# schematic.net
KiCad netlist of a schematic drawn in EAGLE
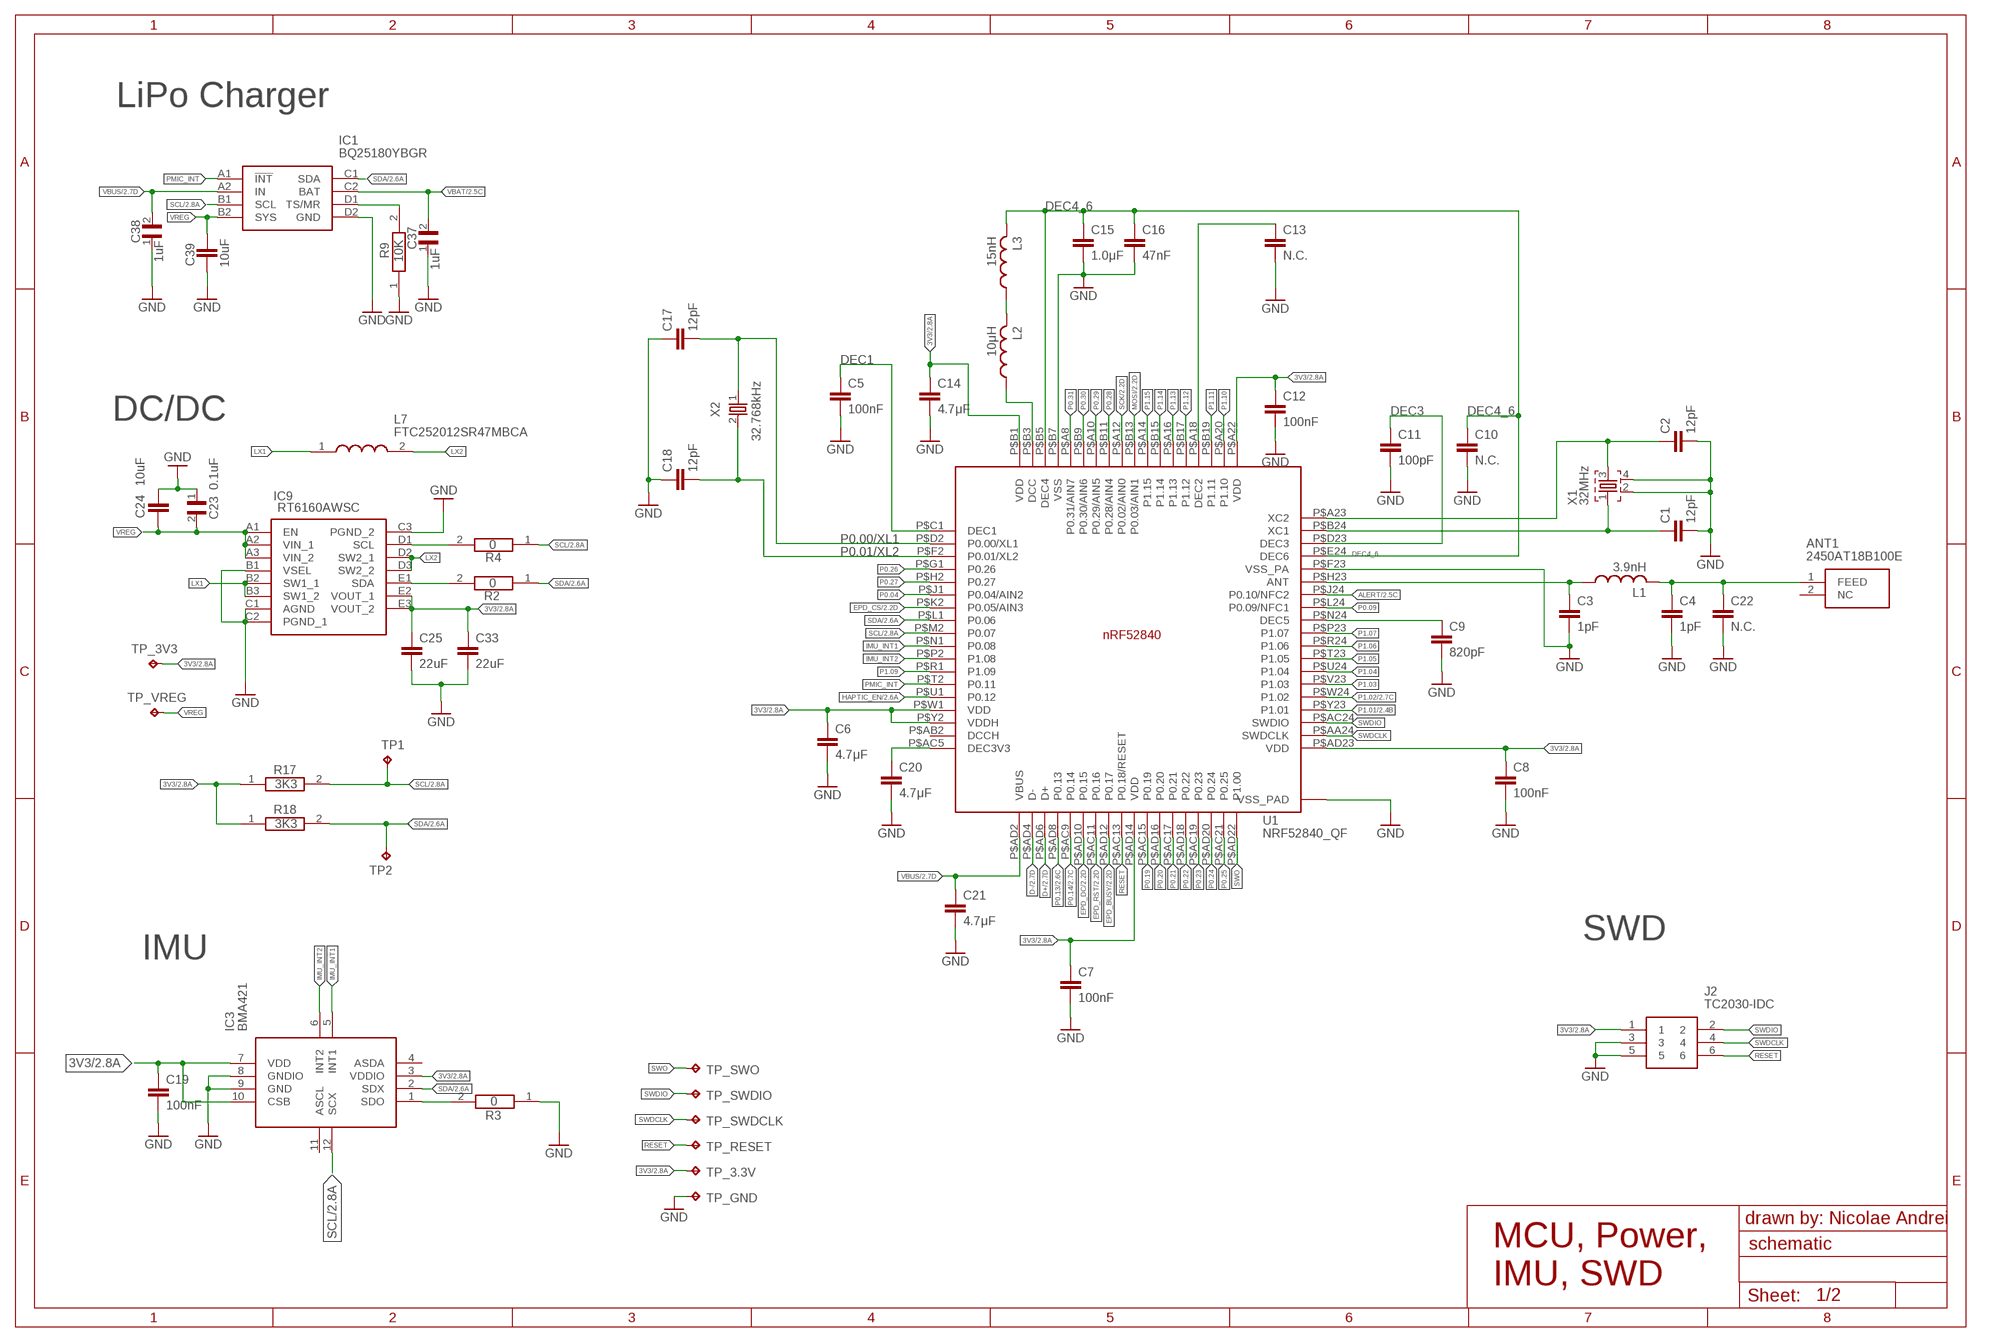
[diagram p0: schematic, sheet 1]
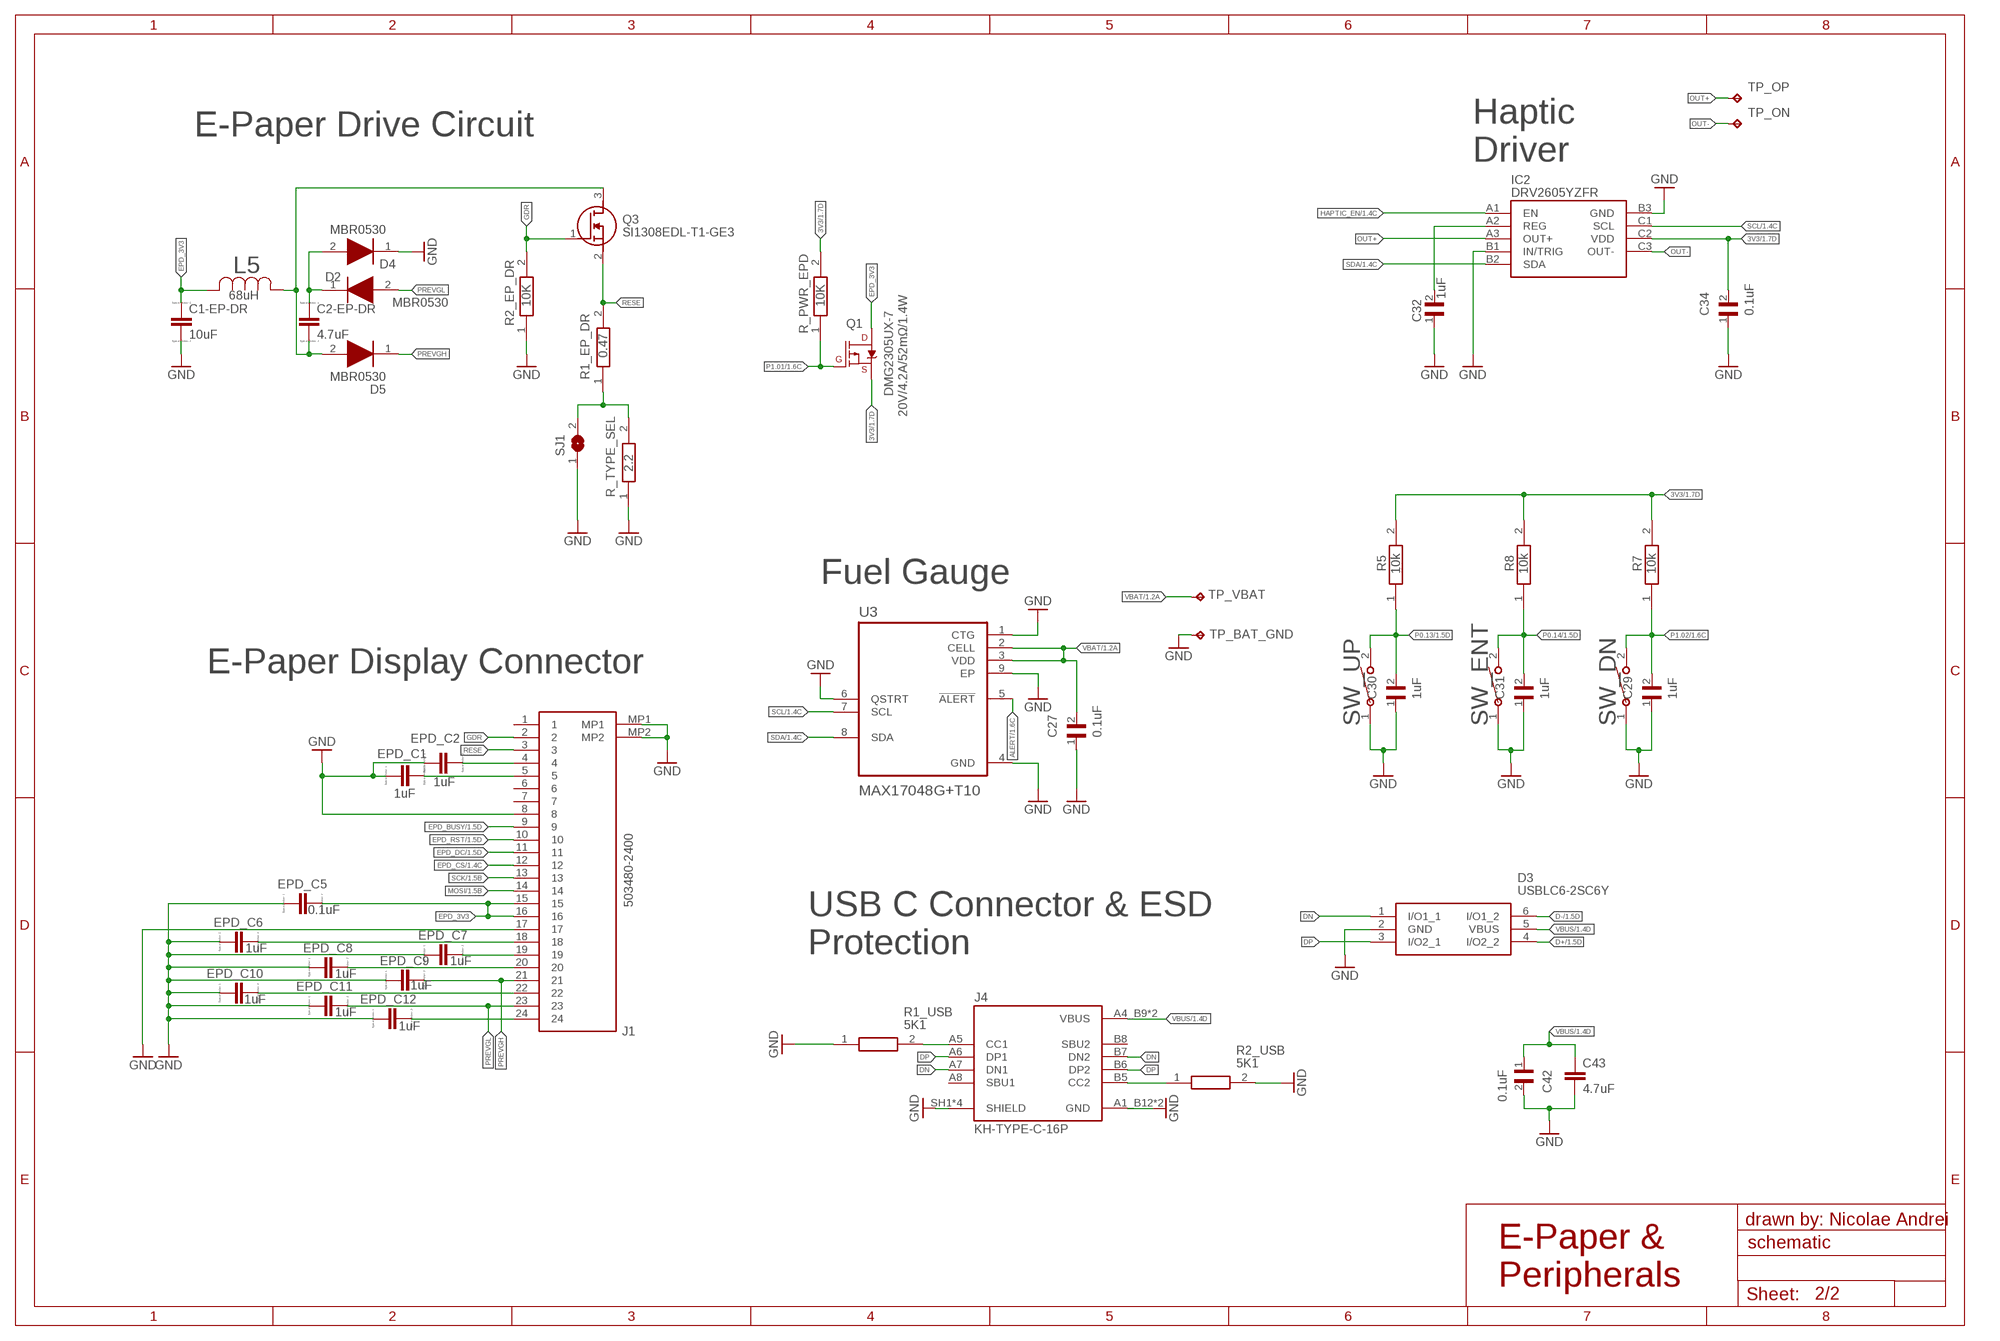
[diagram p1: schematic, sheet 2]

(export (version "E")
  (design (tool "Eeschema 10.0.6"))
  (components
    (comp (ref "C1-EP-DR")
      (value "10uF")
      (footprint "eagle-import:ESP32_C6_LIBRARY_1_ESP32_WROVER_EAGLE-LTSPICE_C0402")
      (libsource (lib "eagle-import") (part "ESP32_C6_LIBRARY_1_ESP32_WROVER_EAGLE-LTSPICE_CC0402"))
    )
    (comp (ref "C2-EP-DR")
      (value "4.7uF")
      (footprint "eagle-import:ESP32_C6_LIBRARY_1_ESP32_WROVER_EAGLE-LTSPICE_C0402")
      (libsource (lib "eagle-import") (part "ESP32_C6_LIBRARY_1_ESP32_WROVER_EAGLE-LTSPICE_CC0402"))
    )
    (comp (ref "C27")
      (value "0.1uF")
      (footprint "eagle-import:GRM011R60J152KE01L_2_CAPC0201X13N")
      (fields (field (name "MF") "Murata") (field (name "MP") "GRM011R60J152KE01L"))
      (libsource (lib "eagle-import") (part "GRM011R60J152KE01L_2_GRM011R60J152KE01L"))
    )
    (comp (ref "C29")
      (value "1uF")
      (footprint "eagle-import:GRM011R60J152KE01L_2_CAPC0201X13N")
      (fields (field (name "MF") "Murata") (field (name "MP") "GRM011R60J152KE01L"))
      (libsource (lib "eagle-import") (part "GRM011R60J152KE01L_2_GRM011R60J152KE01L"))
    )
    (comp (ref "C30")
      (value "1uF")
      (footprint "eagle-import:GRM011R60J152KE01L_2_CAPC0201X13N")
      (fields (field (name "MF") "Murata") (field (name "MP") "GRM011R60J152KE01L"))
      (libsource (lib "eagle-import") (part "GRM011R60J152KE01L_2_GRM011R60J152KE01L"))
    )
    (comp (ref "C31")
      (value "1uF")
      (footprint "eagle-import:GRM011R60J152KE01L_2_CAPC0201X13N")
      (fields (field (name "MF") "Murata") (field (name "MP") "GRM011R60J152KE01L"))
      (libsource (lib "eagle-import") (part "GRM011R60J152KE01L_2_GRM011R60J152KE01L"))
    )
    (comp (ref "C32")
      (value "1uF")
      (footprint "eagle-import:GRM011R60J152KE01L_2_CAPC0201X13N")
      (fields (field (name "MF") "Murata") (field (name "MP") "GRM011R60J152KE01L"))
      (libsource (lib "eagle-import") (part "GRM011R60J152KE01L_2_GRM011R60J152KE01L"))
    )
    (comp (ref "C34")
      (value "0.1uF")
      (footprint "eagle-import:GRM011R60J152KE01L_2_CAPC0201X13N")
      (fields (field (name "MF") "Murata") (field (name "MP") "GRM011R60J152KE01L"))
      (libsource (lib "eagle-import") (part "GRM011R60J152KE01L_2_GRM011R60J152KE01L"))
    )
    (comp (ref "C42")
      (value "0.1uF")
      (footprint "eagle-import:GRM011R60J152KE01L_2_CAPC0201X13N")
      (fields (field (name "MF") "Murata") (field (name "MP") "GRM011R60J152KE01L"))
      (libsource (lib "eagle-import") (part "GRM011R60J152KE01L_2_GRM011R60J152KE01L"))
    )
    (comp (ref "C43")
      (value "4.7uF")
      (footprint "eagle-import:NORDIC_NRF_3_RESC0402_L")
      (libsource (lib "eagle-import") (part "NORDIC_NRF_3_CAPACITOR_0402_L"))
    )
    (comp (ref "D2")
      (value "MBR0530")
      (footprint "eagle-import:ESP32_C6_LIBRARY_5_SOD3716X135N")
      (fields (field (name "MF") "ON Semiconductor"))
      (libsource (lib "eagle-import") (part "ESP32_C6_LIBRARY_5_MBR0530"))
    )
    (comp (ref "D3")
      (value "USBLC6-2SC6Y")
      (footprint "eagle-import:ESP32_C6_LIBRARY_3_SOT95P280X145-6N")
      (fields (field (name "MF") "STMicroelectronics"))
      (libsource (lib "eagle-import") (part "ESP32_C6_LIBRARY_3_USBLC6-2SC6Y"))
    )
    (comp (ref "D4")
      (value "MBR0530")
      (footprint "eagle-import:ESP32_C6_LIBRARY_5_SOD3716X135N")
      (fields (field (name "MF") "ON Semiconductor"))
      (libsource (lib "eagle-import") (part "ESP32_C6_LIBRARY_5_MBR0530"))
    )
    (comp (ref "D5")
      (value "MBR0530")
      (footprint "eagle-import:ESP32_C6_LIBRARY_5_SOD3716X135N")
      (fields (field (name "MF") "ON Semiconductor"))
      (libsource (lib "eagle-import") (part "ESP32_C6_LIBRARY_5_MBR0530"))
    )
    (comp (ref "EPD_C1")
      (value "1uF")
      (footprint "eagle-import:ESP32_C6_LIBRARY_1_ESP32_WROVER_EAGLE-LTSPICE_C0402")
      (libsource (lib "eagle-import") (part "ESP32_C6_LIBRARY_1_ESP32_WROVER_EAGLE-LTSPICE_CC0402"))
    )
    (comp (ref "EPD_C2")
      (value "1uF")
      (footprint "eagle-import:ESP32_C6_LIBRARY_1_ESP32_WROVER_EAGLE-LTSPICE_C0402")
      (libsource (lib "eagle-import") (part "ESP32_C6_LIBRARY_1_ESP32_WROVER_EAGLE-LTSPICE_CC0402"))
    )
    (comp (ref "EPD_C5")
      (value "0.1uF")
      (footprint "eagle-import:ESP32_C6_LIBRARY_1_ESP32_WROVER_EAGLE-LTSPICE_C0402")
      (libsource (lib "eagle-import") (part "ESP32_C6_LIBRARY_1_ESP32_WROVER_EAGLE-LTSPICE_CC0402"))
    )
    (comp (ref "EPD_C6")
      (value "1uF")
      (footprint "eagle-import:ESP32_C6_LIBRARY_1_ESP32_WROVER_EAGLE-LTSPICE_C0402")
      (libsource (lib "eagle-import") (part "ESP32_C6_LIBRARY_1_ESP32_WROVER_EAGLE-LTSPICE_CC0402"))
    )
    (comp (ref "EPD_C7")
      (value "1uF")
      (footprint "eagle-import:ESP32_C6_LIBRARY_1_ESP32_WROVER_EAGLE-LTSPICE_C0402")
      (libsource (lib "eagle-import") (part "ESP32_C6_LIBRARY_1_ESP32_WROVER_EAGLE-LTSPICE_CC0402"))
    )
    (comp (ref "EPD_C8")
      (value "1uF")
      (footprint "eagle-import:ESP32_C6_LIBRARY_1_ESP32_WROVER_EAGLE-LTSPICE_C0402")
      (libsource (lib "eagle-import") (part "ESP32_C6_LIBRARY_1_ESP32_WROVER_EAGLE-LTSPICE_CC0402"))
    )
    (comp (ref "EPD_C9")
      (value "1uF")
      (footprint "eagle-import:ESP32_C6_LIBRARY_1_ESP32_WROVER_EAGLE-LTSPICE_C0402")
      (libsource (lib "eagle-import") (part "ESP32_C6_LIBRARY_1_ESP32_WROVER_EAGLE-LTSPICE_CC0402"))
    )
    (comp (ref "EPD_C10")
      (value "1uF")
      (footprint "eagle-import:ESP32_C6_LIBRARY_1_ESP32_WROVER_EAGLE-LTSPICE_C0402")
      (libsource (lib "eagle-import") (part "ESP32_C6_LIBRARY_1_ESP32_WROVER_EAGLE-LTSPICE_CC0402"))
    )
    (comp (ref "EPD_C11")
      (value "1uF")
      (footprint "eagle-import:ESP32_C6_LIBRARY_1_ESP32_WROVER_EAGLE-LTSPICE_C0402")
      (libsource (lib "eagle-import") (part "ESP32_C6_LIBRARY_1_ESP32_WROVER_EAGLE-LTSPICE_CC0402"))
    )
    (comp (ref "EPD_C12")
      (value "1uF")
      (footprint "eagle-import:ESP32_C6_LIBRARY_1_ESP32_WROVER_EAGLE-LTSPICE_C0402")
      (libsource (lib "eagle-import") (part "ESP32_C6_LIBRARY_1_ESP32_WROVER_EAGLE-LTSPICE_CC0402"))
    )
    (comp (ref "IC2")
      (value "DRV2605YZFR")
      (footprint "eagle-import:DRV2605YZFR_BGA9C50P3X3_144X144X62")
      (libsource (lib "eagle-import") (part "DRV2605YZFR_DRV2605YZFR"))
    )
    (comp (ref "J1")
      (value "503480-2400")
      (footprint "eagle-import:503480-2400_5034802400")
      (fields (field (name "MOUSER_PART_NUMBER") "538-503480-2400"))
      (libsource (lib "eagle-import") (part "503480-2400_503480-2400"))
    )
    (comp (ref "J4")
      (value "KH-TYPE-C-16P")
      (footprint "eagle-import:KH-TYPE-C-16P_KINGHELM_KH-TYPE-C-16P")
      (fields (field (name "MF") "kinghelm"))
      (libsource (lib "eagle-import") (part "KH-TYPE-C-16P_KH-TYPE-C-16P"))
    )
    (comp (ref "L5")
      (value "68uH")
      (footprint "eagle-import:ESP32_C6_LIBRARY_2_IND_4828-WE-TPC_WRE")
      (fields
        (field (name "MANUFACTURER_PART_NUMBER") "744043680")
        (field (name "COPYRIGHT") "Copyright (C) 2024 Ultra Librarian. All rights reserved.")
      )
      (libsource (lib "eagle-import") (part "ESP32_C6_LIBRARY_2_744043680IND_4828-WE-TPC_WRE"))
    )
    (comp (ref "Q1")
      (value "20V/4.2A/52mΩ/1.4W")
      (footprint "eagle-import:ESP32_C6_LIBRARY_4_ESP32_C6_LIBRARY_4_ESP32_C6_LIBRARY_4_ESP32_C6_LIBRARY_4_ESP32_WROVER_SPARKFUN-DISCRETESEMI_SOT23-3")
      (fields (field (name "SPECIFICATII") "DMG2305UX-7"))
      (libsource (lib "eagle-import") (part "ESP32_C6_LIBRARY_4_ESP32_WROVER_SPARKFUN-DISCRETESEMI_MOSFET_PCH-DMG2305UX-7"))
    )
    (comp (ref "Q3")
      (value "SI1308EDL-T1-GE3")
      (footprint "eagle-import:ESP32_C6_LIBRARY_6_SOT65P210X110-3N")
      (fields (field (name "MF") "Vishay Siliconix"))
      (libsource (lib "eagle-import") (part "ESP32_C6_LIBRARY_6_SI1308EDL-T1-GE3"))
    )
    (comp (ref "R1_EP_DR")
      (value "0.47")
      (footprint "eagle-import:CPF0201D7K68C1_0201")
      (libsource (lib "eagle-import") (part "CPF0201D7K68C1_CPF0201D7K68C1"))
    )
    (comp (ref "R1_USB")
      (value "5K1")
      (footprint "eagle-import:CPF0201D7K68C1_0201")
      (libsource (lib "eagle-import") (part "CPF0201D7K68C1_CPF0201D7K68C1"))
    )
    (comp (ref "R2_EP_DR")
      (value "10K")
      (footprint "eagle-import:CPF0201D7K68C1_0201")
      (libsource (lib "eagle-import") (part "CPF0201D7K68C1_CPF0201D7K68C1"))
    )
    (comp (ref "R2_USB")
      (value "5K1")
      (footprint "eagle-import:CPF0201D7K68C1_0201")
      (libsource (lib "eagle-import") (part "CPF0201D7K68C1_CPF0201D7K68C1"))
    )
    (comp (ref "R5")
      (value "10k")
      (footprint "eagle-import:CPF0201D7K68C1_0201")
      (libsource (lib "eagle-import") (part "CPF0201D7K68C1_CPF0201D7K68C1"))
    )
    (comp (ref "R7")
      (value "10k")
      (footprint "eagle-import:CPF0201D7K68C1_0201")
      (libsource (lib "eagle-import") (part "CPF0201D7K68C1_CPF0201D7K68C1"))
    )
    (comp (ref "R8")
      (value "10k")
      (footprint "eagle-import:CPF0201D7K68C1_0201")
      (libsource (lib "eagle-import") (part "CPF0201D7K68C1_CPF0201D7K68C1"))
    )
    (comp (ref "R_PWR_EPD")
      (value "10K")
      (footprint "eagle-import:CPF0201D7K68C1_0201")
      (libsource (lib "eagle-import") (part "CPF0201D7K68C1_CPF0201D7K68C1"))
    )
    (comp (ref "R_TYPE_SEL")
      (value "2.2")
      (footprint "eagle-import:CPF0201D7K68C1_0201")
      (libsource (lib "eagle-import") (part "CPF0201D7K68C1_CPF0201D7K68C1"))
    )
    (comp (ref "SJ1")
      (value "ESP32_C6_LIBRARY_7_JUMPER_SJ")
      (footprint "eagle-import:ESP32_C6_LIBRARY_7_JUMPER_SJ")
      (libsource (lib "eagle-import") (part "ESP32_C6_LIBRARY_7_JUMPER_SJ"))
    )
    (comp (ref "SW_DN")
      (value "2025-10-22_07-23-44_LIBRARY_EVP-AKE31ASW_EVP-AKE31A_PAN")
      (footprint "eagle-import:2025-10-22_07-23-44_LIBRARY_SW_EVP-AKE31A_PAN")
      (fields
        (field (name "MANUFACTURER_PART_NUMBER") "EVP-AKE31A")
        (field (name "COPYRIGHT") "Copyright (C) 2025 Ultra Librarian. All rights reserved.")
      )
      (libsource (lib "eagle-import") (part "2025-10-22_07-23-44_LIBRARY_EVP-AKE31ASW_EVP-AKE31A_PAN"))
    )
    (comp (ref "SW_ENT")
      (value "2025-10-22_07-23-44_LIBRARY_EVP-AKE31ASW_EVP-AKE31A_PAN")
      (footprint "eagle-import:2025-10-22_07-23-44_LIBRARY_SW_EVP-AKE31A_PAN")
      (fields
        (field (name "MANUFACTURER_PART_NUMBER") "EVP-AKE31A")
        (field (name "COPYRIGHT") "Copyright (C) 2025 Ultra Librarian. All rights reserved.")
      )
      (libsource (lib "eagle-import") (part "2025-10-22_07-23-44_LIBRARY_EVP-AKE31ASW_EVP-AKE31A_PAN"))
    )
    (comp (ref "SW_UP")
      (value "2025-10-22_07-23-44_LIBRARY_EVP-AKE31ASW_EVP-AKE31A_PAN")
      (footprint "eagle-import:2025-10-22_07-23-44_LIBRARY_SW_EVP-AKE31A_PAN")
      (fields
        (field (name "MANUFACTURER_PART_NUMBER") "EVP-AKE31A")
        (field (name "COPYRIGHT") "Copyright (C) 2025 Ultra Librarian. All rights reserved.")
      )
      (libsource (lib "eagle-import") (part "2025-10-22_07-23-44_LIBRARY_EVP-AKE31ASW_EVP-AKE31A_PAN"))
    )
    (comp (ref "TP_BAT_GND")
      (value "HECTOR_WATCH_1_TPTP20R")
      (footprint "eagle-import:HECTOR_WATCH_1_TP20R")
      (libsource (lib "eagle-import") (part "HECTOR_WATCH_1_TPTP20R"))
    )
    (comp (ref "TP_ON")
      (value "HECTOR_WATCH_1_TPTP20R")
      (footprint "eagle-import:HECTOR_WATCH_1_TP20R")
      (libsource (lib "eagle-import") (part "HECTOR_WATCH_1_TPTP20R"))
    )
    (comp (ref "TP_OP")
      (value "HECTOR_WATCH_1_TPTP20R")
      (footprint "eagle-import:HECTOR_WATCH_1_TP20R")
      (libsource (lib "eagle-import") (part "HECTOR_WATCH_1_TPTP20R"))
    )
    (comp (ref "TP_VBAT")
      (value "HECTOR_WATCH_1_TPTP20R")
      (footprint "eagle-import:HECTOR_WATCH_1_TP20R")
      (libsource (lib "eagle-import") (part "HECTOR_WATCH_1_TPTP20R"))
    )
    (comp (ref "U3")
      (value "MAX17048G+T10")
      (footprint "eagle-import:ESP32_C6_LIBRARY_SON50P200X200X80-9N")
      (fields (field (name "MF") "Analog Devices"))
      (libsource (lib "eagle-import") (part "ESP32_C6_LIBRARY_MAX17048G+T10"))
    )
    (comp (ref "ANT1")
      (value "2450AT18B100E")
      (footprint "eagle-import:2450AT18B100E_ANTC3216X140N")
      (fields (field (name "MOUSER_PART_NUMBER") "609-2450AT18B100E"))
      (libsource (lib "eagle-import") (part "2450AT18B100E_2450AT18B100E"))
    )
    (comp (ref "C1")
      (value "12pF")
      (footprint "eagle-import:NORDIC_NRF_3_RESC0201_L")
      (libsource (lib "eagle-import") (part "NORDIC_NRF_3_CAPACITOR_0201_L"))
    )
    (comp (ref "C2")
      (value "12pF")
      (footprint "eagle-import:NORDIC_NRF_3_RESC0201_L")
      (libsource (lib "eagle-import") (part "NORDIC_NRF_3_CAPACITOR_0201_L"))
    )
    (comp (ref "C3")
      (value "1pF")
      (footprint "eagle-import:NORDIC_NRF_3_RESC0201_L")
      (libsource (lib "eagle-import") (part "NORDIC_NRF_3_CAPACITOR_0201_L"))
    )
    (comp (ref "C4")
      (value "1pF")
      (footprint "eagle-import:NORDIC_NRF_3_RESC0201_L")
      (libsource (lib "eagle-import") (part "NORDIC_NRF_3_CAPACITOR_0201_L"))
    )
    (comp (ref "C5")
      (value "100nF")
      (footprint "eagle-import:NORDIC_NRF_3_RESC0201_L")
      (libsource (lib "eagle-import") (part "NORDIC_NRF_3_CAPACITOR_0201_L"))
    )
    (comp (ref "C6")
      (value "4.7μF")
      (footprint "eagle-import:NORDIC_NRF_3_RESC0402_L")
      (libsource (lib "eagle-import") (part "NORDIC_NRF_3_CAPACITOR_0402_L"))
    )
    (comp (ref "C7")
      (value "100nF")
      (footprint "eagle-import:NORDIC_NRF_3_RESC0201_L")
      (libsource (lib "eagle-import") (part "NORDIC_NRF_3_CAPACITOR_0201_L"))
    )
    (comp (ref "C8")
      (value "100nF")
      (footprint "eagle-import:NORDIC_NRF_3_RESC0201_L")
      (libsource (lib "eagle-import") (part "NORDIC_NRF_3_CAPACITOR_0201_L"))
    )
    (comp (ref "C9")
      (value "820pF")
      (footprint "eagle-import:NORDIC_NRF_3_RESC0201_L")
      (libsource (lib "eagle-import") (part "NORDIC_NRF_3_CAPACITOR_0201_L"))
    )
    (comp (ref "C10")
      (value "N.C.")
      (footprint "eagle-import:NORDIC_NRF_3_RESC0201_L")
      (libsource (lib "eagle-import") (part "NORDIC_NRF_3_CAPACITOR_0201_L"))
    )
    (comp (ref "C11")
      (value "100pF")
      (footprint "eagle-import:NORDIC_NRF_3_RESC0201_L")
      (libsource (lib "eagle-import") (part "NORDIC_NRF_3_CAPACITOR_0201_L"))
    )
    (comp (ref "C12")
      (value "100nF")
      (footprint "eagle-import:NORDIC_NRF_3_RESC0201_L")
      (libsource (lib "eagle-import") (part "NORDIC_NRF_3_CAPACITOR_0201_L"))
    )
    (comp (ref "C13")
      (value "N.C.")
      (footprint "eagle-import:NORDIC_NRF_3_RESC0201_L")
      (libsource (lib "eagle-import") (part "NORDIC_NRF_3_CAPACITOR_0201_L"))
    )
    (comp (ref "C14")
      (value "4.7μF")
      (footprint "eagle-import:NORDIC_NRF_3_RESC0402_L")
      (libsource (lib "eagle-import") (part "NORDIC_NRF_3_CAPACITOR_0402_L"))
    )
    (comp (ref "C15")
      (value "1.0μF")
      (footprint "eagle-import:NORDIC_NRF_3_RESC0402_L")
      (libsource (lib "eagle-import") (part "NORDIC_NRF_3_CAPACITOR_0402_L"))
    )
    (comp (ref "C16")
      (value "47nF")
      (footprint "eagle-import:NORDIC_NRF_3_RESC0201_L")
      (libsource (lib "eagle-import") (part "NORDIC_NRF_3_CAPACITOR_0201_L"))
    )
    (comp (ref "C17")
      (value "12pF")
      (footprint "eagle-import:NORDIC_NRF_3_RESC0201_L")
      (libsource (lib "eagle-import") (part "NORDIC_NRF_3_CAPACITOR_0201_L"))
    )
    (comp (ref "C18")
      (value "12pF")
      (footprint "eagle-import:NORDIC_NRF_3_RESC0201_L")
      (libsource (lib "eagle-import") (part "NORDIC_NRF_3_CAPACITOR_0201_L"))
    )
    (comp (ref "C19")
      (value "100nF")
      (footprint "eagle-import:NORDIC_NRF_3_RESC0201_L")
      (libsource (lib "eagle-import") (part "NORDIC_NRF_3_CAPACITOR_0201_L"))
    )
    (comp (ref "C20")
      (value "4.7μF")
      (footprint "eagle-import:NORDIC_NRF_3_RESC0402_L")
      (libsource (lib "eagle-import") (part "NORDIC_NRF_3_CAPACITOR_0402_L"))
    )
    (comp (ref "C21")
      (value "4.7μF")
      (footprint "eagle-import:NORDIC_NRF_3_RESC0402_L")
      (libsource (lib "eagle-import") (part "NORDIC_NRF_3_CAPACITOR_0402_L"))
    )
    (comp (ref "C22")
      (value "N.C.")
      (footprint "eagle-import:NORDIC_NRF_3_RESC0201_L")
      (libsource (lib "eagle-import") (part "NORDIC_NRF_3_CAPACITOR_0201_L"))
    )
    (comp (ref "C23")
      (value "0.1uF")
      (footprint "eagle-import:GRM011R60J152KE01L_1_0201")
      (libsource (lib "eagle-import") (part "GRM011R60J152KE01L_1_GRM011R60J152KE01L"))
    )
    (comp (ref "C24")
      (value "10uF")
      (footprint "eagle-import:PERFECT_0402_0402")
      (libsource (lib "eagle-import") (part "PERFECT_0402_CAP_0402"))
    )
    (comp (ref "C25")
      (value "22uF")
      (footprint "eagle-import:PERFECT_0402_0402")
      (libsource (lib "eagle-import") (part "PERFECT_0402_CAP_0402"))
    )
    (comp (ref "C33")
      (value "22uF")
      (footprint "eagle-import:PERFECT_0402_0402")
      (libsource (lib "eagle-import") (part "PERFECT_0402_CAP_0402"))
    )
    (comp (ref "C37")
      (value "1uF")
      (footprint "eagle-import:GRM011R60J152KE01L_1_0201")
      (libsource (lib "eagle-import") (part "GRM011R60J152KE01L_1_GRM011R60J152KE01L"))
    )
    (comp (ref "C38")
      (value "1uF")
      (footprint "eagle-import:GRM011R60J152KE01L_1_0201")
      (libsource (lib "eagle-import") (part "GRM011R60J152KE01L_1_GRM011R60J152KE01L"))
    )
    (comp (ref "C39")
      (value "10uF")
      (footprint "eagle-import:PERFECT_0402_0402")
      (libsource (lib "eagle-import") (part "PERFECT_0402_CAP_0402"))
    )
    (comp (ref "IC1")
      (value "BQ25180YBGR")
      (footprint "eagle-import:BQ25180YBGR_BGA8C40P2X4_100X155X50")
      (fields (field (name "MOUSER_PART_NUMBER") "595-BQ25180YBGR"))
      (libsource (lib "eagle-import") (part "BQ25180YBGR_BQ25180YBGR"))
    )
    (comp (ref "IC3")
      (value "BMA421")
      (footprint "eagle-import:BMA423_BMA423")
      (fields (field (name "ARROW_PART_NUMBER") "BMA423") (field (name "MOUSER_PART_NUMBER") "262-BMA423"))
      (libsource (lib "eagle-import") (part "BMA423_BMA423"))
    )
    (comp (ref "IC9")
      (value "RT6160AWSC")
      (footprint "eagle-import:RT6160AWSC_BGA15C40P3X5_140X230X60")
      (fields (field (name "MOUSER_PART_NUMBER") "835-RT6160AWSC"))
      (libsource (lib "eagle-import") (part "RT6160AWSC_RT6160AWSC"))
    )
    (comp (ref "J2")
      (value "TC2030-IDC")
      (footprint "eagle-import:TC2030-IDC_TC2030IDC")
      (libsource (lib "eagle-import") (part "TC2030-IDC_TC2030-IDC"))
    )
    (comp (ref "L1")
      (value "3.9nH")
      (footprint "eagle-import:NORDIC_NRF_2_RESC0402_L")
      (libsource (lib "eagle-import") (part "NORDIC_NRF_2_INDUCTOR_0402_L"))
    )
    (comp (ref "L2")
      (value "10μH")
      (footprint "eagle-import:NORDIC_NRF_2_RESC0402_L")
      (libsource (lib "eagle-import") (part "NORDIC_NRF_2_INDUCTOR_0402_L"))
    )
    (comp (ref "L3")
      (value "15nH")
      (footprint "eagle-import:NORDIC_NRF_2_RESC0402_L")
      (libsource (lib "eagle-import") (part "NORDIC_NRF_2_INDUCTOR_0402_L"))
    )
    (comp (ref "L7")
      (value "FTC252012SR47MBCA")
      (footprint "eagle-import:MLP2016SR47MT0S1_INDC2016X100N")
      (libsource (lib "eagle-import") (part "MLP2016SR47MT0S1_FTC252012SR47MBCA"))
    )
    (comp (ref "R2")
      (value "0")
      (footprint "eagle-import:CPF0201D7K68C1_0201")
      (libsource (lib "eagle-import") (part "CPF0201D7K68C1_CPF0201D7K68C1"))
    )
    (comp (ref "R3")
      (value "0")
      (footprint "eagle-import:CPF0201D7K68C1_0201")
      (libsource (lib "eagle-import") (part "CPF0201D7K68C1_CPF0201D7K68C1"))
    )
    (comp (ref "R4")
      (value "0")
      (footprint "eagle-import:CPF0201D7K68C1_0201")
      (libsource (lib "eagle-import") (part "CPF0201D7K68C1_CPF0201D7K68C1"))
    )
    (comp (ref "R9")
      (value "10K")
      (footprint "eagle-import:CPF0201D7K68C1_0201")
      (libsource (lib "eagle-import") (part "CPF0201D7K68C1_CPF0201D7K68C1"))
    )
    (comp (ref "R17")
      (value "3K3")
      (footprint "eagle-import:CPF0201D7K68C1_0201")
      (libsource (lib "eagle-import") (part "CPF0201D7K68C1_CPF0201D7K68C1"))
    )
    (comp (ref "R18")
      (value "3K3")
      (footprint "eagle-import:CPF0201D7K68C1_0201")
      (libsource (lib "eagle-import") (part "CPF0201D7K68C1_CPF0201D7K68C1"))
    )
    (comp (ref "TP1")
      (value "HECTOR_WATCH_1_TPTP20R")
      (footprint "eagle-import:HECTOR_WATCH_1_TP20R")
      (libsource (lib "eagle-import") (part "HECTOR_WATCH_1_TPTP20R"))
    )
    (comp (ref "TP2")
      (value "HECTOR_WATCH_1_TPTP20R")
      (footprint "eagle-import:HECTOR_WATCH_1_TP20R")
      (libsource (lib "eagle-import") (part "HECTOR_WATCH_1_TPTP20R"))
    )
    (comp (ref "TP_3.3V")
      (value "HECTOR_WATCH_1_TPTP20R")
      (footprint "eagle-import:HECTOR_WATCH_1_TP20R")
      (libsource (lib "eagle-import") (part "HECTOR_WATCH_1_TPTP20R"))
    )
    (comp (ref "TP_3V3")
      (value "HECTOR_WATCH_1_TPTP20R")
      (footprint "eagle-import:HECTOR_WATCH_1_TP20R")
      (libsource (lib "eagle-import") (part "HECTOR_WATCH_1_TPTP20R"))
    )
    (comp (ref "TP_GND")
      (value "HECTOR_WATCH_1_TPTP20R")
      (footprint "eagle-import:HECTOR_WATCH_1_TP20R")
      (libsource (lib "eagle-import") (part "HECTOR_WATCH_1_TPTP20R"))
    )
    (comp (ref "TP_RESET")
      (value "HECTOR_WATCH_1_TPTP20R")
      (footprint "eagle-import:HECTOR_WATCH_1_TP20R")
      (libsource (lib "eagle-import") (part "HECTOR_WATCH_1_TPTP20R"))
    )
    (comp (ref "TP_SWDCLK")
      (value "HECTOR_WATCH_1_TPTP20R")
      (footprint "eagle-import:HECTOR_WATCH_1_TP20R")
      (libsource (lib "eagle-import") (part "HECTOR_WATCH_1_TPTP20R"))
    )
    (comp (ref "TP_SWDIO")
      (value "HECTOR_WATCH_1_TPTP20R")
      (footprint "eagle-import:HECTOR_WATCH_1_TP20R")
      (libsource (lib "eagle-import") (part "HECTOR_WATCH_1_TPTP20R"))
    )
    (comp (ref "TP_SWO")
      (value "HECTOR_WATCH_1_TPTP20R")
      (footprint "eagle-import:HECTOR_WATCH_1_TP20R")
      (libsource (lib "eagle-import") (part "HECTOR_WATCH_1_TPTP20R"))
    )
    (comp (ref "TP_VREG")
      (value "HECTOR_WATCH_1_TPTP20R")
      (footprint "eagle-import:HECTOR_WATCH_1_TP20R")
      (libsource (lib "eagle-import") (part "HECTOR_WATCH_1_TPTP20R"))
    )
    (comp (ref "U1")
      (value "NRF52840_QF")
      (footprint "eagle-import:NORDIC_NRF_4_AQFN50P700X700X85_HS-74N")
      (libsource (lib "eagle-import") (part "NORDIC_NRF_4_NRF52840_QF"))
    )
    (comp (ref "X1")
      (value "32MHz")
      (footprint "eagle-import:NORDIC_NRF_BT-XTAL_2016_N")
      (libsource (lib "eagle-import") (part "NORDIC_NRF_XTAL_32MHZ"))
    )
    (comp (ref "X2")
      (value "32.768kHz")
      (footprint "eagle-import:NORDIC_NRF_1_XTAL_3215_N")
      (libsource (lib "eagle-import") (part "NORDIC_NRF_1_XTAL_32KHZ"))
    )
  )
  (nets
    (net (code "1") (name "3V3") (class "Default")
      (node (ref "C12") (pin "1") (pinfunction "1_1") (pintype "passive"))
      (node (ref "C14") (pin "1") (pinfunction "1_1") (pintype "passive"))
      (node (ref "C19") (pin "1") (pinfunction "1_1") (pintype "passive"))
      (node (ref "C25") (pin "1") (pinfunction "1_1") (pintype "passive"))
      (node (ref "C33") (pin "1") (pinfunction "1_1") (pintype "passive"))
      (node (ref "C34") (pin "2") (pinfunction "2_2") (pintype "passive"))
      (node (ref "C6") (pin "1") (pinfunction "1_1") (pintype "passive"))
      (node (ref "C7") (pin "1") (pinfunction "1_1") (pintype "passive"))
      (node (ref "C8") (pin "1") (pinfunction "1_1") (pintype "passive"))
      (node (ref "IC2") (pin "C2") (pinfunction "VDD_C2") (pintype "bidirectional"))
      (node (ref "IC3") (pin "10") (pinfunction "CSB_10") (pintype "bidirectional"))
      (node (ref "IC3") (pin "3") (pinfunction "VDDIO_3") (pintype "bidirectional"))
      (node (ref "IC3") (pin "7") (pinfunction "VDD_7") (pintype "bidirectional"))
      (node (ref "IC9") (pin "E2") (pinfunction "VOUT_1_E2") (pintype "bidirectional"))
      (node (ref "IC9") (pin "E3") (pinfunction "VOUT_2_E3") (pintype "bidirectional"))
      (node (ref "J2") (pin "1") (pinfunction "1_1") (pintype "bidirectional"))
      (node (ref "Q1") (pin "2") (pinfunction "S_2") (pintype "bidirectional"))
      (node (ref "R17") (pin "1") (pinfunction "1_1") (pintype "bidirectional"))
      (node (ref "R18") (pin "1") (pinfunction "1_1") (pintype "bidirectional"))
      (node (ref "R5") (pin "2") (pinfunction "2_2") (pintype "bidirectional"))
      (node (ref "R7") (pin "2") (pinfunction "2_2") (pintype "bidirectional"))
      (node (ref "R8") (pin "2") (pinfunction "2_2") (pintype "bidirectional"))
      (node (ref "R_PWR_EPD") (pin "2") (pinfunction "2_2") (pintype "bidirectional"))
      (node (ref "TP_3.3V") (pin "TP") (pinfunction "TP_TP") (pintype "input"))
      (node (ref "TP_3V3") (pin "TP") (pinfunction "TP_TP") (pintype "input"))
      (node (ref "U1") (pin "P$A22") (pinfunction "VDD_P$A22") (pintype "power_in"))
      (node (ref "U1") (pin "P$AD14") (pinfunction "VDD_P$AD14") (pintype "power_in"))
      (node (ref "U1") (pin "P$AD23") (pinfunction "VDD_P$AD23") (pintype "power_in"))
      (node (ref "U1") (pin "P$B1") (pinfunction "VDD_P$B1") (pintype "power_in"))
      (node (ref "U1") (pin "P$W1") (pinfunction "VDD_P$W1") (pintype "power_in"))
      (node (ref "U1") (pin "P$Y2") (pinfunction "VDDH_P$Y2") (pintype "power_in"))
    )
    (net (code "2") (name "ALERT") (class "Default")
      (node (ref "U1") (pin "P$J24") (pinfunction "P0.10/NFC2_P$J24") (pintype "bidirectional"))
      (node (ref "U3") (pin "5") (pinfunction "~{ALERT}_5") (pintype "output"))
    )
    (net (code "3") (name "D+") (class "Default")
      (node (ref "D3") (pin "4") (pinfunction "I/O2_2_4") (pintype "bidirectional"))
      (node (ref "U1") (pin "P$AD6") (pinfunction "D+_P$AD6") (pintype "bidirectional"))
    )
    (net (code "4") (name "D-") (class "Default")
      (node (ref "D3") (pin "6") (pinfunction "I/O1_2_6") (pintype "bidirectional"))
      (node (ref "U1") (pin "P$AD4") (pinfunction "D-_P$AD4") (pintype "bidirectional"))
    )
    (net (code "5") (name "DEC1") (class "Default")
      (node (ref "C5") (pin "1") (pinfunction "1_1") (pintype "passive"))
      (node (ref "U1") (pin "P$C1") (pinfunction "DEC1_P$C1") (pintype "power_in"))
    )
    (net (code "6") (name "DEC3") (class "Default")
      (node (ref "C11") (pin "1") (pinfunction "1_1") (pintype "passive"))
      (node (ref "U1") (pin "P$D23") (pinfunction "DEC3_P$D23") (pintype "bidirectional"))
    )
    (net (code "7") (name "DEC4_6") (class "Default")
      (node (ref "C10") (pin "1") (pinfunction "1_1") (pintype "passive"))
      (node (ref "C15") (pin "1") (pinfunction "1_1") (pintype "passive"))
      (node (ref "C16") (pin "1") (pinfunction "1_1") (pintype "passive"))
      (node (ref "L3") (pin "2") (pinfunction "2_2") (pintype "passive"))
      (node (ref "U1") (pin "P$B5") (pinfunction "DEC4_P$B5") (pintype "power_in"))
      (node (ref "U1") (pin "P$E24") (pinfunction "DEC6_P$E24") (pintype "bidirectional"))
    )
    (net (code "8") (name "DN") (class "Default")
      (node (ref "D3") (pin "1") (pinfunction "I/O1_1_1") (pintype "bidirectional"))
      (node (ref "J4") (pin "A7") (pinfunction "DN1_A7") (pintype "bidirectional"))
      (node (ref "J4") (pin "B7") (pinfunction "DN2_B7") (pintype "bidirectional"))
    )
    (net (code "9") (name "DP") (class "Default")
      (node (ref "D3") (pin "3") (pinfunction "I/O2_1_3") (pintype "bidirectional"))
      (node (ref "J4") (pin "A6") (pinfunction "DP1_A6") (pintype "bidirectional"))
      (node (ref "J4") (pin "B6") (pinfunction "DP2_B6") (pintype "bidirectional"))
    )
    (net (code "10") (name "EPD_3V3") (class "Default")
      (node (ref "C1-EP-DR") (pin "1") (pinfunction "1_1") (pintype "passive"))
      (node (ref "EPD_C5") (pin "2") (pinfunction "2_2") (pintype "passive"))
      (node (ref "J1") (pin "15") (pinfunction "15_15") (pintype "bidirectional"))
      (node (ref "J1") (pin "16") (pinfunction "16_16") (pintype "bidirectional"))
      (node (ref "L5") (pin "2") (pinfunction "2_2") (pintype "passive"))
      (node (ref "Q1") (pin "3") (pinfunction "D_3") (pintype "bidirectional"))
    )
    (net (code "11") (name "EPD_BUSY") (class "Default")
      (node (ref "J1") (pin "9") (pinfunction "9_9") (pintype "bidirectional"))
      (node (ref "U1") (pin "P$AD12") (pinfunction "P0.17_P$AD12") (pintype "bidirectional"))
    )
    (net (code "12") (name "EPD_CS") (class "Default")
      (node (ref "J1") (pin "12") (pinfunction "12_12") (pintype "bidirectional"))
      (node (ref "U1") (pin "P$K2") (pinfunction "P0.05/AIN3_P$K2") (pintype "bidirectional"))
    )
    (net (code "13") (name "EPD_DC") (class "Default")
      (node (ref "J1") (pin "11") (pinfunction "11_11") (pintype "bidirectional"))
      (node (ref "U1") (pin "P$AD10") (pinfunction "P0.15_P$AD10") (pintype "bidirectional"))
    )
    (net (code "14") (name "EPD_RST") (class "Default")
      (node (ref "J1") (pin "10") (pinfunction "10_10") (pintype "bidirectional"))
      (node (ref "U1") (pin "P$AC11") (pinfunction "P0.16_P$AC11") (pintype "bidirectional"))
    )
    (net (code "15") (name "GDR") (class "Default")
      (node (ref "J1") (pin "2") (pinfunction "2_2") (pintype "bidirectional"))
      (node (ref "Q3") (pin "1") (pinfunction "G_1") (pintype "bidirectional"))
      (node (ref "R2_EP_DR") (pin "2") (pinfunction "2_2") (pintype "bidirectional"))
    )
    (net (code "16") (name "GND") (class "Default")
      (node (ref "C1") (pin "2") (pinfunction "2_2") (pintype "passive"))
      (node (ref "C1-EP-DR") (pin "2") (pinfunction "2_2") (pintype "passive"))
      (node (ref "C10") (pin "2") (pinfunction "2_2") (pintype "passive"))
      (node (ref "C11") (pin "2") (pinfunction "2_2") (pintype "passive"))
      (node (ref "C12") (pin "2") (pinfunction "2_2") (pintype "passive"))
      (node (ref "C13") (pin "2") (pinfunction "2_2") (pintype "passive"))
      (node (ref "C14") (pin "2") (pinfunction "2_2") (pintype "passive"))
      (node (ref "C15") (pin "2") (pinfunction "2_2") (pintype "passive"))
      (node (ref "C16") (pin "2") (pinfunction "2_2") (pintype "passive"))
      (node (ref "C17") (pin "1") (pinfunction "1_1") (pintype "passive"))
      (node (ref "C18") (pin "1") (pinfunction "1_1") (pintype "passive"))
      (node (ref "C19") (pin "2") (pinfunction "2_2") (pintype "passive"))
      (node (ref "C2") (pin "2") (pinfunction "2_2") (pintype "passive"))
      (node (ref "C20") (pin "2") (pinfunction "2_2") (pintype "passive"))
      (node (ref "C21") (pin "2") (pinfunction "2_2") (pintype "passive"))
      (node (ref "C22") (pin "2") (pinfunction "2_2") (pintype "passive"))
      (node (ref "C23") (pin "1") (pinfunction "1_1") (pintype "passive"))
      (node (ref "C24") (pin "1") (pinfunction "1_1") (pintype "passive"))
      (node (ref "C25") (pin "2") (pinfunction "2_2") (pintype "passive"))
      (node (ref "C27") (pin "1") (pinfunction "1_1") (pintype "passive"))
      (node (ref "C29") (pin "1") (pinfunction "1_1") (pintype "passive"))
      (node (ref "C3") (pin "2") (pinfunction "2_2") (pintype "passive"))
      (node (ref "C30") (pin "1") (pinfunction "1_1") (pintype "passive"))
      (node (ref "C31") (pin "1") (pinfunction "1_1") (pintype "passive"))
      (node (ref "C32") (pin "1") (pinfunction "1_1") (pintype "passive"))
      (node (ref "C33") (pin "2") (pinfunction "2_2") (pintype "passive"))
      (node (ref "C34") (pin "1") (pinfunction "1_1") (pintype "passive"))
      (node (ref "C37") (pin "1") (pinfunction "1_1") (pintype "passive"))
      (node (ref "C38") (pin "1") (pinfunction "1_1") (pintype "passive"))
      (node (ref "C39") (pin "2") (pinfunction "2_2") (pintype "passive"))
      (node (ref "C4") (pin "2") (pinfunction "2_2") (pintype "passive"))
      (node (ref "C42") (pin "2") (pinfunction "2_2") (pintype "passive"))
      (node (ref "C43") (pin "2") (pinfunction "2_2") (pintype "passive"))
      (node (ref "C5") (pin "2") (pinfunction "2_2") (pintype "passive"))
      (node (ref "C6") (pin "2") (pinfunction "2_2") (pintype "passive"))
      (node (ref "C7") (pin "2") (pinfunction "2_2") (pintype "passive"))
      (node (ref "C8") (pin "2") (pinfunction "2_2") (pintype "passive"))
      (node (ref "C9") (pin "2") (pinfunction "2_2") (pintype "passive"))
      (node (ref "D2") (pin "1") (pinfunction "K_1") (pintype "bidirectional"))
      (node (ref "D3") (pin "2") (pinfunction "GND_2") (pintype "bidirectional"))
      (node (ref "EPD_C1") (pin "1") (pinfunction "1_1") (pintype "passive"))
      (node (ref "EPD_C10") (pin "1") (pinfunction "1_1") (pintype "passive"))
      (node (ref "EPD_C11") (pin "1") (pinfunction "1_1") (pintype "passive"))
      (node (ref "EPD_C12") (pin "1") (pinfunction "1_1") (pintype "passive"))
      (node (ref "EPD_C2") (pin "1") (pinfunction "1_1") (pintype "passive"))
      (node (ref "EPD_C5") (pin "1") (pinfunction "1_1") (pintype "passive"))
      (node (ref "EPD_C6") (pin "1") (pinfunction "1_1") (pintype "passive"))
      (node (ref "EPD_C7") (pin "1") (pinfunction "1_1") (pintype "passive"))
      (node (ref "EPD_C8") (pin "1") (pinfunction "1_1") (pintype "passive"))
      (node (ref "EPD_C9") (pin "1") (pinfunction "1_1") (pintype "passive"))
      (node (ref "IC1") (pin "D2") (pinfunction "GND_D2") (pintype "bidirectional"))
      (node (ref "IC2") (pin "B1") (pinfunction "IN/TRIG_B1") (pintype "bidirectional"))
      (node (ref "IC2") (pin "B3") (pinfunction "GND_B3") (pintype "bidirectional"))
      (node (ref "IC3") (pin "8") (pinfunction "GNDIO_8") (pintype "bidirectional"))
      (node (ref "IC3") (pin "9") (pinfunction "GND_9") (pintype "bidirectional"))
      (node (ref "IC9") (pin "B1") (pinfunction "VSEL_B1") (pintype "bidirectional"))
      (node (ref "IC9") (pin "C1") (pinfunction "AGND_C1") (pintype "bidirectional"))
      (node (ref "IC9") (pin "C2") (pinfunction "PGND_1_C2") (pintype "bidirectional"))
      (node (ref "IC9") (pin "C3") (pinfunction "PGND_2_C3") (pintype "bidirectional"))
      (node (ref "J1") (pin "17") (pinfunction "17_17") (pintype "bidirectional"))
      (node (ref "J1") (pin "8") (pinfunction "8_8") (pintype "bidirectional"))
      (node (ref "J1") (pin "MP1") (pinfunction "MP1_MP1") (pintype "bidirectional"))
      (node (ref "J1") (pin "MP2") (pinfunction "MP2_MP2") (pintype "bidirectional"))
      (node (ref "J2") (pin "3") (pinfunction "3_3") (pintype "bidirectional"))
      (node (ref "J2") (pin "5") (pinfunction "5_5") (pintype "bidirectional"))
      (node (ref "J4") (pin "A12_B1") (pinfunction "GND_A12_B1") (pintype "power_in"))
      (node (ref "J4") (pin "A1_B12") (pinfunction "GND_A1_B12") (pintype "power_in"))
      (node (ref "J4") (pin "SH1") (pinfunction "SHIELD_SH1") (pintype "passive"))
      (node (ref "J4") (pin "SH2") (pinfunction "SHIELD_SH2") (pintype "passive"))
      (node (ref "J4") (pin "SH3") (pinfunction "SHIELD_SH3") (pintype "passive"))
      (node (ref "J4") (pin "SH4") (pinfunction "SHIELD_SH4") (pintype "passive"))
      (node (ref "R1_USB") (pin "1") (pinfunction "1_1") (pintype "bidirectional"))
      (node (ref "R2_EP_DR") (pin "1") (pinfunction "1_1") (pintype "bidirectional"))
      (node (ref "R2_USB") (pin "2") (pinfunction "2_2") (pintype "bidirectional"))
      (node (ref "R3") (pin "1") (pinfunction "1_1") (pintype "bidirectional"))
      (node (ref "R9") (pin "1") (pinfunction "1_1") (pintype "bidirectional"))
      (node (ref "R_TYPE_SEL") (pin "1") (pinfunction "1_1") (pintype "bidirectional"))
      (node (ref "SJ1") (pin "1") (pinfunction "1_1") (pintype "passive"))
      (node (ref "SW_DN") (pin "1") (pinfunction "1_1") (pintype "passive"))
      (node (ref "SW_ENT") (pin "1") (pinfunction "1_1") (pintype "passive"))
      (node (ref "SW_UP") (pin "1") (pinfunction "1_1") (pintype "passive"))
      (node (ref "TP_BAT_GND") (pin "TP") (pinfunction "TP_TP") (pintype "input"))
      (node (ref "TP_GND") (pin "TP") (pinfunction "TP_TP") (pintype "input"))
      (node (ref "U1") (pin "P$74") (pinfunction "VSS_PAD_P$74") (pintype "bidirectional"))
      (node (ref "U1") (pin "P$75") (pinfunction "VSS_PAD_P$75") (pintype "bidirectional"))
      (node (ref "U1") (pin "P$76") (pinfunction "VSS_PAD_P$76") (pintype "bidirectional"))
      (node (ref "U1") (pin "P$77") (pinfunction "VSS_PAD_P$77") (pintype "bidirectional"))
      (node (ref "U1") (pin "P$78") (pinfunction "VSS_PAD_P$78") (pintype "bidirectional"))
      (node (ref "U1") (pin "P$79") (pinfunction "VSS_PAD_P$79") (pintype "bidirectional"))
      (node (ref "U1") (pin "P$80") (pinfunction "VSS_PAD_P$80") (pintype "bidirectional"))
      (node (ref "U1") (pin "P$81") (pinfunction "VSS_PAD_P$81") (pintype "bidirectional"))
      (node (ref "U1") (pin "P$82") (pinfunction "VSS_PAD_P$82") (pintype "bidirectional"))
      (node (ref "U1") (pin "P$83") (pinfunction "VSS_PAD_P$83") (pintype "bidirectional"))
      (node (ref "U1") (pin "P$84") (pinfunction "VSS_PAD_P$84") (pintype "bidirectional"))
      (node (ref "U1") (pin "P$85") (pinfunction "VSS_PAD_P$85") (pintype "bidirectional"))
      (node (ref "U1") (pin "P$86") (pinfunction "VSS_PAD_P$86") (pintype "bidirectional"))
      (node (ref "U1") (pin "P$87") (pinfunction "VSS_PAD_P$87") (pintype "bidirectional"))
      (node (ref "U1") (pin "P$88") (pinfunction "VSS_PAD_P$88") (pintype "bidirectional"))
      (node (ref "U1") (pin "P$89") (pinfunction "VSS_PAD_P$89") (pintype "bidirectional"))
      (node (ref "U1") (pin "P$90") (pinfunction "VSS_PAD_P$90") (pintype "bidirectional"))
      (node (ref "U1") (pin "P$B7") (pinfunction "VSS_P$B7") (pintype "power_in"))
      (node (ref "U1") (pin "P$F23") (pinfunction "VSS_PA_P$F23") (pintype "bidirectional"))
      (node (ref "U3") (pin "1") (pinfunction "CTG_1") (pintype "power_in"))
      (node (ref "U3") (pin "4") (pinfunction "GND_4") (pintype "power_in"))
      (node (ref "U3") (pin "6") (pinfunction "QSTRT_6") (pintype "input"))
      (node (ref "U3") (pin "9") (pinfunction "EP_9") (pintype "power_in"))
      (node (ref "X1") (pin "2") (pinfunction "2_2") (pintype "passive"))
      (node (ref "X1") (pin "4") (pinfunction "4_4") (pintype "passive"))
    )
    (net (code "17") (name "HAPTIC_EN") (class "Default")
      (node (ref "IC2") (pin "A1") (pinfunction "EN_A1") (pintype "bidirectional"))
      (node (ref "U1") (pin "P$U1") (pinfunction "P0.12_P$U1") (pintype "bidirectional"))
    )
    (net (code "18") (name "IMU_INT1") (class "Default")
      (node (ref "IC3") (pin "5") (pinfunction "INT1_5") (pintype "bidirectional"))
      (node (ref "U1") (pin "P$N1") (pinfunction "P0.08_P$N1") (pintype "bidirectional"))
    )
    (net (code "19") (name "IMU_INT2") (class "Default")
      (node (ref "IC3") (pin "6") (pinfunction "INT2_6") (pintype "bidirectional"))
      (node (ref "U1") (pin "P$P2") (pinfunction "P1.08_P$P2") (pintype "bidirectional"))
    )
    (net (code "20") (name "LX1") (class "Default")
      (node (ref "IC9") (pin "B2") (pinfunction "SW1_1_B2") (pintype "bidirectional"))
      (node (ref "IC9") (pin "B3") (pinfunction "SW1_2_B3") (pintype "bidirectional"))
      (node (ref "L7") (pin "1") (pinfunction "1_1") (pintype "bidirectional"))
    )
    (net (code "21") (name "LX2") (class "Default")
      (node (ref "IC9") (pin "D2") (pinfunction "SW2_1_D2") (pintype "bidirectional"))
      (node (ref "IC9") (pin "D3") (pinfunction "SW2_2_D3") (pintype "bidirectional"))
      (node (ref "L7") (pin "2") (pinfunction "2_2") (pintype "bidirectional"))
    )
    (net (code "22") (name "MOSI") (class "Default")
      (node (ref "J1") (pin "14") (pinfunction "14_14") (pintype "bidirectional"))
      (node (ref "U1") (pin "P$B13") (pinfunction "P0.03/AIN1_P$B13") (pintype "bidirectional"))
    )
    (net (code "23") (name "Net-(ANT1-FEED)") (class "Default")
      (node (ref "ANT1") (pin "1") (pinfunction "FEED_1") (pintype "input"))
      (node (ref "C22") (pin "1") (pinfunction "1_1") (pintype "passive"))
      (node (ref "C4") (pin "1") (pinfunction "1_1") (pintype "passive"))
      (node (ref "L1") (pin "2") (pinfunction "2_2") (pintype "passive"))
    )
    (net (code "24") (name "Net-(D2-A)") (class "Default")
      (node (ref "C2-EP-DR") (pin "1") (pinfunction "1_1") (pintype "passive"))
      (node (ref "D2") (pin "2") (pinfunction "A_2") (pintype "bidirectional"))
      (node (ref "D4") (pin "1") (pinfunction "K_1") (pintype "bidirectional"))
    )
    (net (code "25") (name "Net-(D5-A)") (class "Default")
      (node (ref "C2-EP-DR") (pin "2") (pinfunction "2_2") (pintype "passive"))
      (node (ref "D5") (pin "2") (pinfunction "A_2") (pintype "bidirectional"))
      (node (ref "L5") (pin "1") (pinfunction "1_1") (pintype "passive"))
      (node (ref "Q3") (pin "3") (pinfunction "D_3") (pintype "bidirectional"))
    )
    (net (code "26") (name "Net-(EPD_C1-Pad2)") (class "Default")
      (node (ref "EPD_C1") (pin "2") (pinfunction "2_2") (pintype "passive"))
      (node (ref "J1") (pin "5") (pinfunction "5_5") (pintype "bidirectional"))
    )
    (net (code "27") (name "Net-(EPD_C2-Pad2)") (class "Default")
      (node (ref "EPD_C2") (pin "2") (pinfunction "2_2") (pintype "passive"))
      (node (ref "J1") (pin "4") (pinfunction "4_4") (pintype "bidirectional"))
    )
    (net (code "28") (name "Net-(EPD_C6-Pad2)") (class "Default")
      (node (ref "EPD_C6") (pin "2") (pinfunction "2_2") (pintype "passive"))
      (node (ref "J1") (pin "18") (pinfunction "18_18") (pintype "bidirectional"))
    )
    (net (code "29") (name "Net-(EPD_C7-Pad2)") (class "Default")
      (node (ref "EPD_C7") (pin "2") (pinfunction "2_2") (pintype "passive"))
      (node (ref "J1") (pin "19") (pinfunction "19_19") (pintype "bidirectional"))
    )
    (net (code "30") (name "Net-(EPD_C8-Pad2)") (class "Default")
      (node (ref "EPD_C8") (pin "2") (pinfunction "2_2") (pintype "passive"))
      (node (ref "J1") (pin "20") (pinfunction "20_20") (pintype "bidirectional"))
    )
    (net (code "31") (name "Net-(EPD_C10-Pad2)") (class "Default")
      (node (ref "EPD_C10") (pin "2") (pinfunction "2_2") (pintype "passive"))
      (node (ref "J1") (pin "22") (pinfunction "22_22") (pintype "bidirectional"))
    )
    (net (code "32") (name "Net-(EPD_C12-Pad2)") (class "Default")
      (node (ref "EPD_C12") (pin "2") (pinfunction "2_2") (pintype "passive"))
      (node (ref "J1") (pin "24") (pinfunction "24_24") (pintype "bidirectional"))
    )
    (net (code "33") (name "Net-(IC1-TS{slash}MR)") (class "Default")
      (node (ref "IC1") (pin "D1") (pinfunction "TS/MR_D1") (pintype "bidirectional"))
      (node (ref "R9") (pin "2") (pinfunction "2_2") (pintype "bidirectional"))
    )
    (net (code "34") (name "Net-(IC2-REG)") (class "Default")
      (node (ref "C32") (pin "2") (pinfunction "2_2") (pintype "passive"))
      (node (ref "IC2") (pin "A2") (pinfunction "REG_A2") (pintype "bidirectional"))
    )
    (net (code "35") (name "Net-(IC3-SDO)") (class "Default")
      (node (ref "IC3") (pin "1") (pinfunction "SDO_1") (pintype "bidirectional"))
      (node (ref "R3") (pin "2") (pinfunction "2_2") (pintype "bidirectional"))
    )
    (net (code "36") (name "Net-(IC9-SCL)") (class "Default")
      (node (ref "IC9") (pin "D1") (pinfunction "SCL_D1") (pintype "bidirectional"))
      (node (ref "R4") (pin "2") (pinfunction "2_2") (pintype "bidirectional"))
    )
    (net (code "37") (name "Net-(IC9-SDA)") (class "Default")
      (node (ref "IC9") (pin "E1") (pinfunction "SDA_E1") (pintype "bidirectional"))
      (node (ref "R2") (pin "2") (pinfunction "2_2") (pintype "bidirectional"))
    )
    (net (code "38") (name "Net-(J4-CC1)") (class "Default")
      (node (ref "J4") (pin "A5") (pinfunction "CC1_A5") (pintype "bidirectional"))
      (node (ref "R1_USB") (pin "2") (pinfunction "2_2") (pintype "bidirectional"))
    )
    (net (code "39") (name "Net-(J4-CC2)") (class "Default")
      (node (ref "J4") (pin "B5") (pinfunction "CC2_B5") (pintype "bidirectional"))
      (node (ref "R2_USB") (pin "1") (pinfunction "1_1") (pintype "bidirectional"))
    )
    (net (code "40") (name "Net-(L2-Pad2)") (class "Default")
      (node (ref "L2") (pin "2") (pinfunction "2_2") (pintype "passive"))
      (node (ref "L3") (pin "1") (pinfunction "1_1") (pintype "passive"))
    )
    (net (code "41") (name "Net-(R1_EP_DR-Pad1)") (class "Default")
      (node (ref "R1_EP_DR") (pin "1") (pinfunction "1_1") (pintype "bidirectional"))
      (node (ref "R_TYPE_SEL") (pin "2") (pinfunction "2_2") (pintype "bidirectional"))
      (node (ref "SJ1") (pin "2") (pinfunction "2_2") (pintype "passive"))
    )
    (net (code "42") (name "Net-(U1-ANT)") (class "Default")
      (node (ref "C3") (pin "1") (pinfunction "1_1") (pintype "passive"))
      (node (ref "L1") (pin "1") (pinfunction "1_1") (pintype "passive"))
      (node (ref "U1") (pin "P$H23") (pinfunction "ANT_P$H23") (pintype "bidirectional"))
    )
    (net (code "43") (name "Net-(U1-DCC)") (class "Default")
      (node (ref "L2") (pin "1") (pinfunction "1_1") (pintype "passive"))
      (node (ref "U1") (pin "P$B3") (pinfunction "DCC_P$B3") (pintype "output"))
    )
    (net (code "44") (name "Net-(U1-DEC2)") (class "Default")
      (node (ref "C13") (pin "1") (pinfunction "1_1") (pintype "passive"))
      (node (ref "U1") (pin "P$A18") (pinfunction "DEC2_P$A18") (pintype "bidirectional"))
    )
    (net (code "45") (name "Net-(U1-DEC3V3)") (class "Default")
      (node (ref "C20") (pin "1") (pinfunction "1_1") (pintype "passive"))
      (node (ref "U1") (pin "P$AC5") (pinfunction "DEC3V3_P$AC5") (pintype "bidirectional"))
    )
    (net (code "46") (name "Net-(U1-DEC5)") (class "Default")
      (node (ref "C9") (pin "1") (pinfunction "1_1") (pintype "passive"))
      (node (ref "U1") (pin "P$N24") (pinfunction "DEC5_P$N24") (pintype "bidirectional"))
    )
    (net (code "47") (name "Net-(U1-XC1)") (class "Default")
      (node (ref "C1") (pin "1") (pinfunction "1_1") (pintype "passive"))
      (node (ref "U1") (pin "P$B24") (pinfunction "XC1_P$B24") (pintype "input"))
      (node (ref "X1") (pin "1") (pinfunction "1_1") (pintype "passive"))
    )
    (net (code "48") (name "Net-(U1-XC2)") (class "Default")
      (node (ref "C2") (pin "1") (pinfunction "1_1") (pintype "passive"))
      (node (ref "U1") (pin "P$A23") (pinfunction "XC2_P$A23") (pintype "output"))
      (node (ref "X1") (pin "3") (pinfunction "3_3") (pintype "passive"))
    )
    (net (code "49") (name "OUT+") (class "Default")
      (node (ref "IC2") (pin "A3") (pinfunction "OUT+_A3") (pintype "bidirectional"))
      (node (ref "TP_OP") (pin "TP") (pinfunction "TP_TP") (pintype "input"))
    )
    (net (code "50") (name "OUT-") (class "Default")
      (node (ref "IC2") (pin "C3") (pinfunction "OUT-_C3") (pintype "bidirectional"))
      (node (ref "TP_ON") (pin "TP") (pinfunction "TP_TP") (pintype "input"))
    )
    (net (code "51") (name "P0.00{slash}XL1") (class "Default")
      (node (ref "C17") (pin "2") (pinfunction "2_2") (pintype "passive"))
      (node (ref "U1") (pin "P$D2") (pinfunction "P0.00/XL1_P$D2") (pintype "bidirectional"))
      (node (ref "X2") (pin "1") (pinfunction "1_1") (pintype "passive"))
    )
    (net (code "52") (name "P0.01{slash}XL2") (class "Default")
      (node (ref "C18") (pin "2") (pinfunction "2_2") (pintype "passive"))
      (node (ref "U1") (pin "P$F2") (pinfunction "P0.01/XL2_P$F2") (pintype "bidirectional"))
      (node (ref "X2") (pin "2") (pinfunction "2_2") (pintype "passive"))
    )
    (net (code "53") (name "P0.04") (class "Default")
      (node (ref "U1") (pin "P$J1") (pinfunction "P0.04/AIN2_P$J1") (pintype "bidirectional"))
    )
    (net (code "54") (name "P0.09") (class "Default")
      (node (ref "U1") (pin "P$L24") (pinfunction "P0.09/NFC1_P$L24") (pintype "bidirectional"))
    )
    (net (code "55") (name "P0.13") (class "Default")
      (node (ref "C30") (pin "2") (pinfunction "2_2") (pintype "passive"))
      (node (ref "R5") (pin "1") (pinfunction "1_1") (pintype "bidirectional"))
      (node (ref "SW_UP") (pin "2") (pinfunction "2_2") (pintype "passive"))
      (node (ref "U1") (pin "P$AD8") (pinfunction "P0.13_P$AD8") (pintype "bidirectional"))
    )
    (net (code "56") (name "P0.14") (class "Default")
      (node (ref "C31") (pin "2") (pinfunction "2_2") (pintype "passive"))
      (node (ref "R8") (pin "1") (pinfunction "1_1") (pintype "bidirectional"))
      (node (ref "SW_ENT") (pin "2") (pinfunction "2_2") (pintype "passive"))
      (node (ref "U1") (pin "P$AC9") (pinfunction "P0.14_P$AC9") (pintype "bidirectional"))
    )
    (net (code "57") (name "P0.19") (class "Default")
      (node (ref "U1") (pin "P$AC15") (pinfunction "P0.19_P$AC15") (pintype "bidirectional"))
    )
    (net (code "58") (name "P0.20") (class "Default")
      (node (ref "U1") (pin "P$AD16") (pinfunction "P0.20_P$AD16") (pintype "bidirectional"))
    )
    (net (code "59") (name "P0.21") (class "Default")
      (node (ref "U1") (pin "P$AC17") (pinfunction "P0.21_P$AC17") (pintype "bidirectional"))
    )
    (net (code "60") (name "P0.22") (class "Default")
      (node (ref "U1") (pin "P$AD18") (pinfunction "P0.22_P$AD18") (pintype "bidirectional"))
    )
    (net (code "61") (name "P0.23") (class "Default")
      (node (ref "U1") (pin "P$AC19") (pinfunction "P0.23_P$AC19") (pintype "bidirectional"))
    )
    (net (code "62") (name "P0.24") (class "Default")
      (node (ref "U1") (pin "P$AD20") (pinfunction "P0.24_P$AD20") (pintype "bidirectional"))
    )
    (net (code "63") (name "P0.25") (class "Default")
      (node (ref "U1") (pin "P$AC21") (pinfunction "P0.25_P$AC21") (pintype "bidirectional"))
    )
    (net (code "64") (name "P0.26") (class "Default")
      (node (ref "U1") (pin "P$G1") (pinfunction "P0.26_P$G1") (pintype "bidirectional"))
    )
    (net (code "65") (name "P0.27") (class "Default")
      (node (ref "U1") (pin "P$H2") (pinfunction "P0.27_P$H2") (pintype "bidirectional"))
    )
    (net (code "66") (name "P0.28") (class "Default")
      (node (ref "U1") (pin "P$B11") (pinfunction "P0.28/AIN4_P$B11") (pintype "bidirectional"))
    )
    (net (code "67") (name "P0.29") (class "Default")
      (node (ref "U1") (pin "P$A10") (pinfunction "P0.29/AIN5_P$A10") (pintype "bidirectional"))
    )
    (net (code "68") (name "P0.30") (class "Default")
      (node (ref "U1") (pin "P$B9") (pinfunction "P0.30/AIN6_P$B9") (pintype "bidirectional"))
    )
    (net (code "69") (name "P0.31") (class "Default")
      (node (ref "U1") (pin "P$A8") (pinfunction "P0.31/AIN7_P$A8") (pintype "bidirectional"))
    )
    (net (code "70") (name "P1.01") (class "Default")
      (node (ref "Q1") (pin "1") (pinfunction "G_1") (pintype "bidirectional"))
      (node (ref "R_PWR_EPD") (pin "1") (pinfunction "1_1") (pintype "bidirectional"))
      (node (ref "U1") (pin "P$Y23") (pinfunction "P1.01_P$Y23") (pintype "bidirectional"))
    )
    (net (code "71") (name "P1.02") (class "Default")
      (node (ref "C29") (pin "2") (pinfunction "2_2") (pintype "passive"))
      (node (ref "R7") (pin "1") (pinfunction "1_1") (pintype "bidirectional"))
      (node (ref "SW_DN") (pin "2") (pinfunction "2_2") (pintype "passive"))
      (node (ref "U1") (pin "P$W24") (pinfunction "P1.02_P$W24") (pintype "bidirectional"))
    )
    (net (code "72") (name "P1.03") (class "Default")
      (node (ref "U1") (pin "P$V23") (pinfunction "P1.03_P$V23") (pintype "bidirectional"))
    )
    (net (code "73") (name "P1.04") (class "Default")
      (node (ref "U1") (pin "P$U24") (pinfunction "P1.04_P$U24") (pintype "bidirectional"))
    )
    (net (code "74") (name "P1.05") (class "Default")
      (node (ref "U1") (pin "P$T23") (pinfunction "P1.05_P$T23") (pintype "bidirectional"))
    )
    (net (code "75") (name "P1.06") (class "Default")
      (node (ref "U1") (pin "P$R24") (pinfunction "P1.06_P$R24") (pintype "bidirectional"))
    )
    (net (code "76") (name "P1.07") (class "Default")
      (node (ref "U1") (pin "P$P23") (pinfunction "P1.07_P$P23") (pintype "bidirectional"))
    )
    (net (code "77") (name "P1.09") (class "Default")
      (node (ref "U1") (pin "P$R1") (pinfunction "P1.09_P$R1") (pintype "bidirectional"))
    )
    (net (code "78") (name "P1.10") (class "Default")
      (node (ref "U1") (pin "P$A20") (pinfunction "P1.10_P$A20") (pintype "bidirectional"))
    )
    (net (code "79") (name "P1.11") (class "Default")
      (node (ref "U1") (pin "P$B19") (pinfunction "P1.11_P$B19") (pintype "bidirectional"))
    )
    (net (code "80") (name "P1.12") (class "Default")
      (node (ref "U1") (pin "P$B17") (pinfunction "P1.12_P$B17") (pintype "bidirectional"))
    )
    (net (code "81") (name "P1.13") (class "Default")
      (node (ref "U1") (pin "P$A16") (pinfunction "P1.13_P$A16") (pintype "bidirectional"))
    )
    (net (code "82") (name "P1.14") (class "Default")
      (node (ref "U1") (pin "P$B15") (pinfunction "P1.14_P$B15") (pintype "bidirectional"))
    )
    (net (code "83") (name "P1.15") (class "Default")
      (node (ref "U1") (pin "P$A14") (pinfunction "P1.15_P$A14") (pintype "bidirectional"))
    )
    (net (code "84") (name "PMIC_INT") (class "Default")
      (node (ref "IC1") (pin "A1") (pinfunction "~{INT}_A1") (pintype "bidirectional"))
      (node (ref "U1") (pin "P$T2") (pinfunction "P0.11_P$T2") (pintype "bidirectional"))
    )
    (net (code "85") (name "PREVGH") (class "Default")
      (node (ref "D5") (pin "1") (pinfunction "K_1") (pintype "bidirectional"))
      (node (ref "EPD_C9") (pin "2") (pinfunction "2_2") (pintype "passive"))
      (node (ref "J1") (pin "21") (pinfunction "21_21") (pintype "bidirectional"))
    )
    (net (code "86") (name "PREVGL") (class "Default")
      (node (ref "D4") (pin "2") (pinfunction "A_2") (pintype "bidirectional"))
      (node (ref "EPD_C11") (pin "2") (pinfunction "2_2") (pintype "passive"))
      (node (ref "J1") (pin "23") (pinfunction "23_23") (pintype "bidirectional"))
    )
    (net (code "87") (name "RESE") (class "Default")
      (node (ref "J1") (pin "3") (pinfunction "3_3") (pintype "bidirectional"))
      (node (ref "Q3") (pin "2") (pinfunction "S_2") (pintype "bidirectional"))
      (node (ref "R1_EP_DR") (pin "2") (pinfunction "2_2") (pintype "bidirectional"))
    )
    (net (code "88") (name "RESET") (class "Default")
      (node (ref "J2") (pin "6") (pinfunction "6_6") (pintype "bidirectional"))
      (node (ref "TP_RESET") (pin "TP") (pinfunction "TP_TP") (pintype "input"))
      (node (ref "U1") (pin "P$AC13") (pinfunction "P0.18/RESET_P$AC13") (pintype "bidirectional"))
    )
    (net (code "89") (name "SCK") (class "Default")
      (node (ref "J1") (pin "13") (pinfunction "13_13") (pintype "bidirectional"))
      (node (ref "U1") (pin "P$A12") (pinfunction "P0.02/AIN0_P$A12") (pintype "bidirectional"))
    )
    (net (code "90") (name "SCL") (class "Default")
      (node (ref "IC1") (pin "B1") (pinfunction "SCL_B1") (pintype "bidirectional"))
      (node (ref "IC2") (pin "C1") (pinfunction "SCL_C1") (pintype "bidirectional"))
      (node (ref "IC3") (pin "12") (pinfunction "SCX_12") (pintype "bidirectional"))
      (node (ref "R17") (pin "2") (pinfunction "2_2") (pintype "bidirectional"))
      (node (ref "R4") (pin "1") (pinfunction "1_1") (pintype "bidirectional"))
      (node (ref "TP1") (pin "TP") (pinfunction "TP_TP") (pintype "input"))
      (node (ref "U1") (pin "P$M2") (pinfunction "P0.07_P$M2") (pintype "bidirectional"))
      (node (ref "U3") (pin "7") (pinfunction "SCL_7") (pintype "input"))
    )
    (net (code "91") (name "SDA") (class "Default")
      (node (ref "IC1") (pin "C1") (pinfunction "SDA_C1") (pintype "bidirectional"))
      (node (ref "IC2") (pin "B2") (pinfunction "SDA_B2") (pintype "bidirectional"))
      (node (ref "IC3") (pin "2") (pinfunction "SDX_2") (pintype "bidirectional"))
      (node (ref "R18") (pin "2") (pinfunction "2_2") (pintype "bidirectional"))
      (node (ref "R2") (pin "1") (pinfunction "1_1") (pintype "bidirectional"))
      (node (ref "TP2") (pin "TP") (pinfunction "TP_TP") (pintype "input"))
      (node (ref "U1") (pin "P$L1") (pinfunction "P0.06_P$L1") (pintype "bidirectional"))
      (node (ref "U3") (pin "8") (pinfunction "SDA_8") (pintype "bidirectional"))
    )
    (net (code "92") (name "SWDCLK") (class "Default")
      (node (ref "J2") (pin "4") (pinfunction "4_4") (pintype "bidirectional"))
      (node (ref "TP_SWDCLK") (pin "TP") (pinfunction "TP_TP") (pintype "input"))
      (node (ref "U1") (pin "P$AA24") (pinfunction "SWDCLK_P$AA24") (pintype "input"))
    )
    (net (code "93") (name "SWDIO") (class "Default")
      (node (ref "J2") (pin "2") (pinfunction "2_2") (pintype "bidirectional"))
      (node (ref "TP_SWDIO") (pin "TP") (pinfunction "TP_TP") (pintype "input"))
      (node (ref "U1") (pin "P$AC24") (pinfunction "SWDIO_P$AC24") (pintype "bidirectional"))
    )
    (net (code "94") (name "SWO") (class "Default")
      (node (ref "TP_SWO") (pin "TP") (pinfunction "TP_TP") (pintype "input"))
      (node (ref "U1") (pin "P$AD22") (pinfunction "P1.00_P$AD22") (pintype "bidirectional"))
    )
    (net (code "95") (name "VBAT") (class "Default")
      (node (ref "C27") (pin "2") (pinfunction "2_2") (pintype "passive"))
      (node (ref "C37") (pin "2") (pinfunction "2_2") (pintype "passive"))
      (node (ref "IC1") (pin "C2") (pinfunction "BAT_C2") (pintype "bidirectional"))
      (node (ref "TP_VBAT") (pin "TP") (pinfunction "TP_TP") (pintype "input"))
      (node (ref "U3") (pin "2") (pinfunction "CELL_2") (pintype "power_in"))
      (node (ref "U3") (pin "3") (pinfunction "VDD_3") (pintype "power_in"))
    )
    (net (code "96") (name "VBUS") (class "Default")
      (node (ref "C21") (pin "1") (pinfunction "1_1") (pintype "passive"))
      (node (ref "C38") (pin "2") (pinfunction "2_2") (pintype "passive"))
      (node (ref "C42") (pin "1") (pinfunction "1_1") (pintype "passive"))
      (node (ref "C43") (pin "1") (pinfunction "1_1") (pintype "passive"))
      (node (ref "D3") (pin "5") (pinfunction "VBUS_5") (pintype "bidirectional"))
      (node (ref "IC1") (pin "A2") (pinfunction "IN_A2") (pintype "bidirectional"))
      (node (ref "J4") (pin "A4_B9") (pinfunction "VBUS_A4_B9") (pintype "power_in"))
      (node (ref "J4") (pin "A9_B4") (pinfunction "VBUS_A9_B4") (pintype "power_in"))
      (node (ref "U1") (pin "P$AD2") (pinfunction "VBUS_P$AD2") (pintype "power_in"))
    )
    (net (code "97") (name "VREG") (class "Default")
      (node (ref "C23") (pin "2") (pinfunction "2_2") (pintype "passive"))
      (node (ref "C24") (pin "2") (pinfunction "2_2") (pintype "passive"))
      (node (ref "C39") (pin "1") (pinfunction "1_1") (pintype "passive"))
      (node (ref "IC1") (pin "B2") (pinfunction "SYS_B2") (pintype "bidirectional"))
      (node (ref "IC9") (pin "A1") (pinfunction "EN_A1") (pintype "bidirectional"))
      (node (ref "IC9") (pin "A2") (pinfunction "VIN_1_A2") (pintype "bidirectional"))
      (node (ref "IC9") (pin "A3") (pinfunction "VIN_2_A3") (pintype "bidirectional"))
      (node (ref "TP_VREG") (pin "TP") (pinfunction "TP_TP") (pintype "input"))
    )
    (net (code "98") (name "unconnected-(ANT1-NC-Pad2)") (class "Default")
      (node (ref "ANT1") (pin "2") (pinfunction "NC_2") (pintype "no_connect"))
    )
    (net (code "99") (name "unconnected-(IC3-ASCL-Pad11)") (class "Default")
      (node (ref "IC3") (pin "11") (pinfunction "ASCL_11") (pintype "bidirectional"))
    )
    (net (code "100") (name "unconnected-(IC3-ASDA-Pad4)") (class "Default")
      (node (ref "IC3") (pin "4") (pinfunction "ASDA_4") (pintype "bidirectional"))
    )
    (net (code "101") (name "unconnected-(J1-Pad1)") (class "Default")
      (node (ref "J1") (pin "1") (pinfunction "1_1") (pintype "bidirectional"))
    )
    (net (code "102") (name "unconnected-(J1-Pad6)") (class "Default")
      (node (ref "J1") (pin "6") (pinfunction "6_6") (pintype "bidirectional"))
    )
    (net (code "103") (name "unconnected-(J1-Pad7)") (class "Default")
      (node (ref "J1") (pin "7") (pinfunction "7_7") (pintype "bidirectional"))
    )
    (net (code "104") (name "unconnected-(J4-SBU1-PadA8)") (class "Default")
      (node (ref "J4") (pin "A8") (pinfunction "SBU1_A8") (pintype "bidirectional"))
    )
    (net (code "105") (name "unconnected-(J4-SBU2-PadB8)") (class "Default")
      (node (ref "J4") (pin "B8") (pinfunction "SBU2_B8") (pintype "bidirectional"))
    )
    (net (code "106") (name "unconnected-(U1-DCCH-PadP$AB2)") (class "Default")
      (node (ref "U1") (pin "P$AB2") (pinfunction "DCCH_P$AB2") (pintype "bidirectional"))
    )
  )
)
